# MBP_Universal_Upgrade.net
KiCad netlist of a schematic drawn in Altium Designer
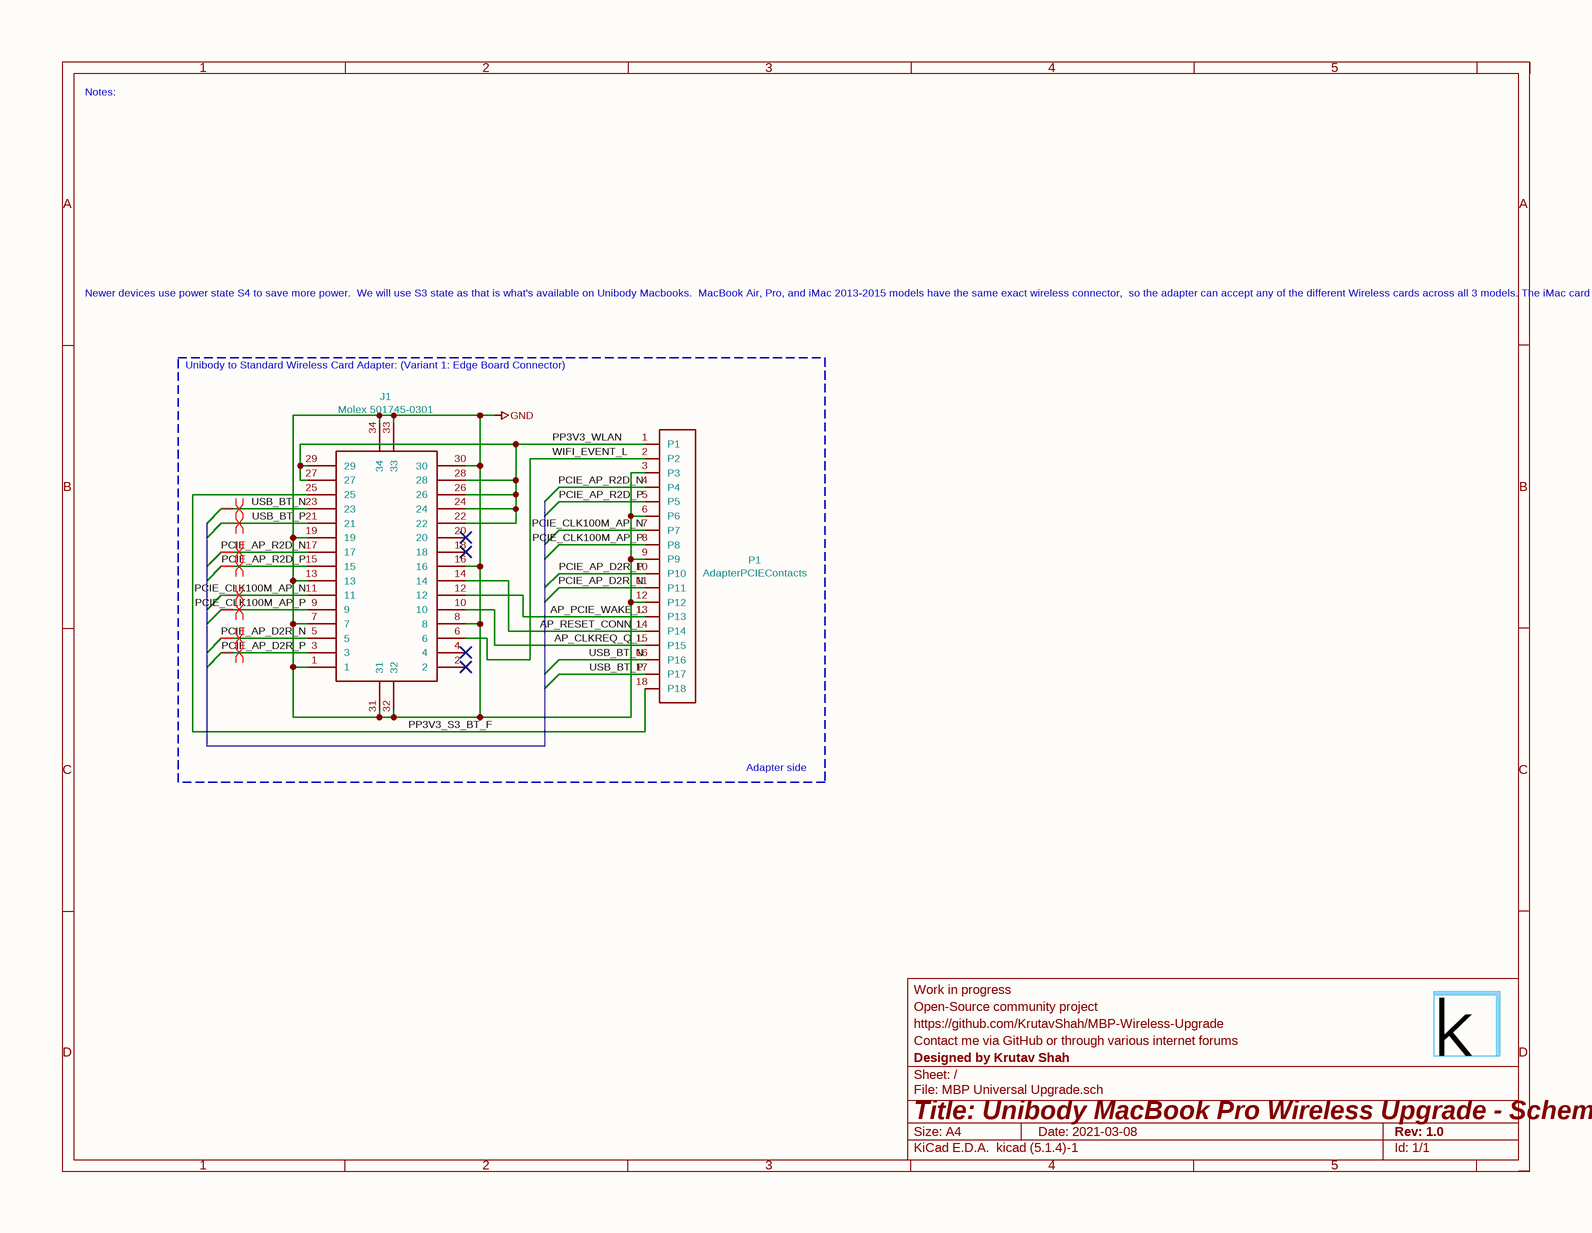
[diagram p0: MBP Universal Upgrade.SchDoc]

(export (version "E")
  (design (tool "Eeschema 10.0.6"))
  (components
    (comp (ref "J1")
      (value "Molex 501745-0301")
      (description "Board to Board & Mezzanine Connectors 0.4 BB PLUG ASSY H=2 EMBSTP PKG")
      (fields
        (field (name "MOUSER PART NUMBER") "538-501745-0301")
        (field (name "MANUFACTURER_PART_NUMBER") "501745-0301")
      )
      (libsource (lib "SamacSys_Parts") (part "501745-0301"))
    )
    (comp (ref "P1")
      (value "AdapterPCIEContacts")
      (libsource (lib "MBPWirelessParts") (part "AdapterPCIEContacts"))
    )
  )
  (nets
    (net (code "1") (name "/AP_CLKREQ_Q_L") (class "Default")
      (node (ref "J1") (pin "10") (pinfunction "10_10") (pintype "passive"))
      (node (ref "P1") (pin "15") (pinfunction "P15_15") (pintype "passive"))
    )
    (net (code "2") (name "/AP_PCIE_WAKE_L") (class "Default")
      (node (ref "J1") (pin "12") (pinfunction "12_12") (pintype "passive"))
      (node (ref "P1") (pin "13") (pinfunction "P13_13") (pintype "passive"))
    )
    (net (code "3") (name "/AP_RESET_CONN_L") (class "Default")
      (node (ref "J1") (pin "14") (pinfunction "14_14") (pintype "passive"))
      (node (ref "P1") (pin "14") (pinfunction "P14_14") (pintype "passive"))
    )
    (net (code "4") (name "/PCIE_AP_D2R_N") (class "Default")
      (node (ref "J1") (pin "5") (pinfunction "5_5") (pintype "passive"))
      (node (ref "P1") (pin "11") (pinfunction "P11_11") (pintype "passive"))
    )
    (net (code "5") (name "/PCIE_AP_D2R_P") (class "Default")
      (node (ref "J1") (pin "3") (pinfunction "3_3") (pintype "passive"))
      (node (ref "P1") (pin "10") (pinfunction "P10_10") (pintype "passive"))
    )
    (net (code "6") (name "/PCIE_AP_R2D_N") (class "Default")
      (node (ref "J1") (pin "17") (pinfunction "17_17") (pintype "passive"))
      (node (ref "P1") (pin "4") (pinfunction "P4_4") (pintype "passive"))
    )
    (net (code "7") (name "/PCIE_AP_R2D_P") (class "Default")
      (node (ref "J1") (pin "15") (pinfunction "15_15") (pintype "passive"))
      (node (ref "P1") (pin "5") (pinfunction "P5_5") (pintype "passive"))
    )
    (net (code "8") (name "/PCIE_CLK100M_AP_N") (class "Default")
      (node (ref "J1") (pin "11") (pinfunction "11_11") (pintype "passive"))
      (node (ref "P1") (pin "7") (pinfunction "P7_7") (pintype "passive"))
    )
    (net (code "9") (name "/PCIE_CLK100M_AP_P") (class "Default")
      (node (ref "J1") (pin "9") (pinfunction "9_9") (pintype "passive"))
      (node (ref "P1") (pin "8") (pinfunction "P8_8") (pintype "passive"))
    )
    (net (code "10") (name "/PP3V3_S3_BT_F") (class "Default")
      (node (ref "J1") (pin "25") (pinfunction "25_25") (pintype "passive"))
      (node (ref "P1") (pin "18") (pinfunction "P18_18") (pintype "passive"))
    )
    (net (code "11") (name "/PP3V3_WLAN") (class "Default")
      (node (ref "J1") (pin "22") (pinfunction "22_22") (pintype "passive"))
      (node (ref "J1") (pin "24") (pinfunction "24_24") (pintype "passive"))
      (node (ref "J1") (pin "26") (pinfunction "26_26") (pintype "passive"))
      (node (ref "J1") (pin "27") (pinfunction "27_27") (pintype "passive"))
      (node (ref "J1") (pin "28") (pinfunction "28_28") (pintype "passive"))
      (node (ref "J1") (pin "29") (pinfunction "29_29") (pintype "passive"))
      (node (ref "P1") (pin "1") (pinfunction "P1_1") (pintype "passive"))
    )
    (net (code "12") (name "/USB_BT_N") (class "Default")
      (node (ref "J1") (pin "23") (pinfunction "23_23") (pintype "passive"))
      (node (ref "P1") (pin "16") (pinfunction "P16_16") (pintype "passive"))
    )
    (net (code "13") (name "/USB_BT_P") (class "Default")
      (node (ref "J1") (pin "21") (pinfunction "21_21") (pintype "passive"))
      (node (ref "P1") (pin "17") (pinfunction "P17_17") (pintype "passive"))
    )
    (net (code "14") (name "/WIFI_EVENT_L") (class "Default")
      (node (ref "J1") (pin "6") (pinfunction "6_6") (pintype "passive"))
      (node (ref "P1") (pin "2") (pinfunction "P2_2") (pintype "passive"))
    )
    (net (code "15") (name "GND") (class "Default")
      (node (ref "J1") (pin "1") (pinfunction "1_1") (pintype "passive"))
      (node (ref "J1") (pin "13") (pinfunction "13_13") (pintype "passive"))
      (node (ref "J1") (pin "16") (pinfunction "16_16") (pintype "passive"))
      (node (ref "J1") (pin "19") (pinfunction "19_19") (pintype "passive"))
      (node (ref "J1") (pin "30") (pinfunction "30_30") (pintype "passive"))
      (node (ref "J1") (pin "31") (pinfunction "31_31") (pintype "passive"))
      (node (ref "J1") (pin "32") (pinfunction "32_32") (pintype "passive"))
      (node (ref "J1") (pin "33") (pinfunction "33_33") (pintype "passive"))
      (node (ref "J1") (pin "34") (pinfunction "34_34") (pintype "passive"))
      (node (ref "J1") (pin "7") (pinfunction "7_7") (pintype "passive"))
      (node (ref "J1") (pin "8") (pinfunction "8_8") (pintype "passive"))
      (node (ref "P1") (pin "12") (pinfunction "P12_12") (pintype "passive"))
      (node (ref "P1") (pin "3") (pinfunction "P3_3") (pintype "passive"))
      (node (ref "P1") (pin "6") (pinfunction "P6_6") (pintype "passive"))
      (node (ref "P1") (pin "9") (pinfunction "P9_9") (pintype "passive"))
    )
    (net (code "16") (name "unconnected-(J1-Pad2)") (class "Default")
      (node (ref "J1") (pin "2") (pinfunction "2_2") (pintype "passive+no_connect"))
    )
    (net (code "17") (name "unconnected-(J1-Pad4)") (class "Default")
      (node (ref "J1") (pin "4") (pinfunction "4_4") (pintype "passive+no_connect"))
    )
    (net (code "18") (name "unconnected-(J1-Pad18)") (class "Default")
      (node (ref "J1") (pin "18") (pinfunction "18_18") (pintype "passive+no_connect"))
    )
    (net (code "19") (name "unconnected-(J1-Pad20)") (class "Default")
      (node (ref "J1") (pin "20") (pinfunction "20_20") (pintype "passive+no_connect"))
    )
  )
)
